# Sensors.net
KiCad netlist of a schematic drawn in Altium Designer
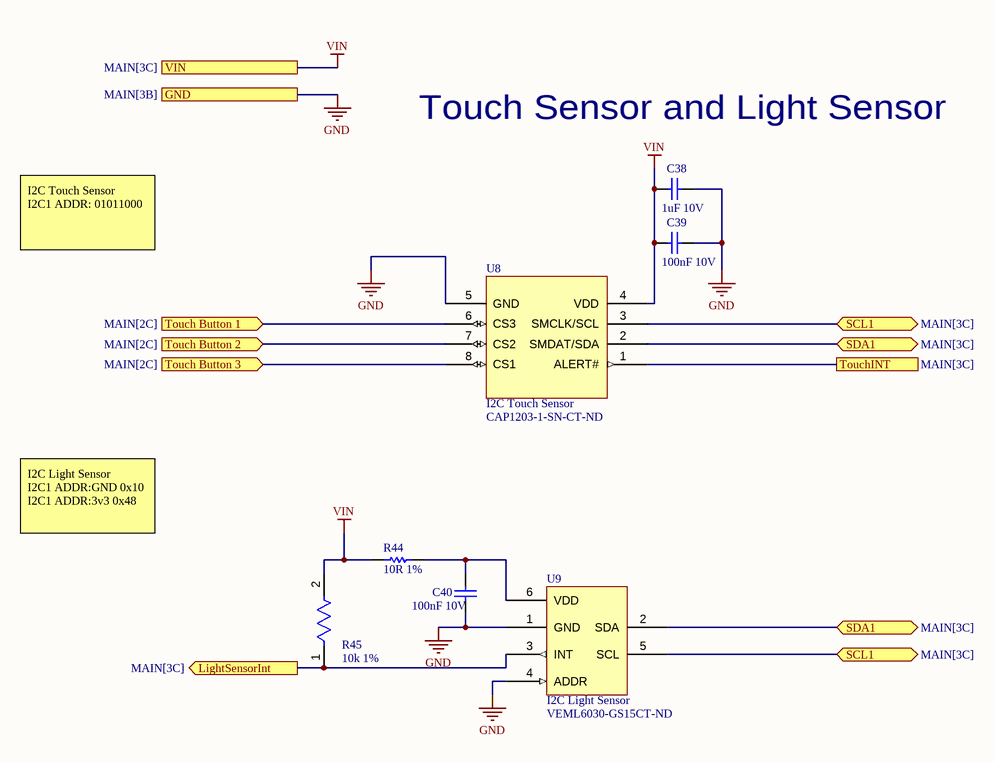
[diagram p0: Sensors.SchDoc]

(export (version "E")
  (design (tool "Eeschema 10.0.6"))
  (components
    (comp (ref "C38")
      (value "1uF 10V")
      (footprint "CAPC0402(1005)60_N")
      (description "CAP 1uF 10V ±10% 0402 (1005 Metric) Thickness 0.6mm SMD")
      (fields (field (name "TOLERANCE") "Â±10%"))
      (libsource (lib "Altium Content Vault") (part "CAP"))
    )
    (comp (ref "C39")
      (value "100nF 10V")
      (footprint "CAPC0402(1005)60_L")
      (description "CAP 100nF 10V ±5% 0402 (1005 Metric) Thickness 0.6mm SMD")
      (fields (field (name "TOLERANCE") "Â±5%"))
      (libsource (lib "Altium Content Vault") (part "CAP"))
    )
    (comp (ref "C40")
      (value "100nF 10V")
      (footprint "CAPC0402(1005)60_L")
      (description "CAP 100nF 10V ±5% 0402 (1005 Metric) Thickness 0.6mm SMD")
      (fields (field (name "TOLERANCE") "Â±5%"))
      (libsource (lib "Altium Content Vault") (part "CAP"))
    )
    (comp (ref "R44")
      (value "10R 1%")
      (footprint "RESC0402(1005)_N")
      (description "10R 0.063W 1% 0402 (1005 Metric)  SMD")
      (fields (field (name "POWER") "0.063 W") (field (name "TOLERANCE") "1 %"))
      (libsource (lib "Altium Content Vault") (part "RES"))
    )
    (comp (ref "R45")
      (value "10k 1%")
      (footprint "FP-CRCW0402-e3-IPC_C")
      (description "RES Thick Film, 10kΩ, 1%, 0.063W, 100ppm/°C, 0402")
      (fields (field (name "TOLERANCE") "1%"))
      (libsource (lib "Altium Content Vault") (part "1029c3af85768c4190bb7ad29bc67b5"))
    )
    (comp (ref "U8")
      (value "I2C Touch Sensor")
      (footprint "CAP1203-1-SN-TR")
      (description "Sensor Controller Capacitive 3-CH I2C 8-Pin SOIC T/R")
      (fields
        (field (name "MANUFACTURER") "Microchip")
        (field (name "MANUFACTURER PART NUMBER") "CAP1203-1-SN-TR")
        (field (name "SUPPLIER PART NUMBER 1") "CAP1203-1-SN-CT-ND")
      )
      (libsource (lib "ESE516A2") (part "CAP1203-1-SN-TR"))
    )
    (comp (ref "U9")
      (value "I2C Light Sensor")
      (footprint "CAC-65P200X200-6N")
      (description "HIGH ACCURACY AMBIENT LIGHT SENS")
      (fields
        (field (name "MANUFACTURER") "Vishay Semiconductors")
        (field (name "MANUFACTURER PART NUMBER") "VEML6030-GS15")
        (field (name "SUPPLIER PART NUMBER 1") "VEML6030-GS15CT-ND")
      )
      (libsource (lib "ESE516A2") (part "VEML6030-GS15"))
    )
  )
  (nets
    (net (code "1") (name "/LightSensorInt") (class "Default")
      (node (ref "R45") (pin "1") (pinfunction "1_1") (pintype "passive"))
      (node (ref "U9") (pin "3") (pinfunction "INT_3") (pintype "output"))
    )
    (net (code "2") (name "/SCL1") (class "Default")
      (node (ref "U8") (pin "3") (pinfunction "SMCLK/SCL_3") (pintype "open_collector"))
      (node (ref "U9") (pin "5") (pinfunction "SCL_5") (pintype "open_collector"))
    )
    (net (code "3") (name "/SDA1") (class "Default")
      (node (ref "U8") (pin "2") (pinfunction "SMDAT/SDA_2") (pintype "open_collector"))
      (node (ref "U9") (pin "2") (pinfunction "SDA_2") (pintype "open_collector"))
    )
    (net (code "4") (name "/Touch Button 1") (class "Default")
      (node (ref "U8") (pin "6") (pinfunction "CS3_6") (pintype "bidirectional"))
    )
    (net (code "5") (name "/Touch Button 2") (class "Default")
      (node (ref "U8") (pin "7") (pinfunction "CS2_7") (pintype "bidirectional"))
    )
    (net (code "6") (name "/Touch Button 3") (class "Default")
      (node (ref "U8") (pin "8") (pinfunction "CS1_8") (pintype "bidirectional"))
    )
    (net (code "7") (name "/TouchINT") (class "Default")
      (node (ref "U8") (pin "1") (pinfunction "ALERT#_1") (pintype "output"))
    )
    (net (code "8") (name "GND") (class "Default")
      (node (ref "C38") (pin "2") (pinfunction "2_2") (pintype "passive"))
      (node (ref "C39") (pin "2") (pinfunction "2_2") (pintype "passive"))
      (node (ref "C40") (pin "1") (pinfunction "1_1") (pintype "passive"))
      (node (ref "U8") (pin "5") (pinfunction "GND_5") (pintype "power_in"))
      (node (ref "U9") (pin "1") (pinfunction "GND_1") (pintype "power_in"))
      (node (ref "U9") (pin "4") (pinfunction "ADDR_4") (pintype "input"))
    )
    (net (code "9") (name "Net-(U9-VDD)") (class "Default")
      (node (ref "C40") (pin "2") (pinfunction "2_2") (pintype "passive"))
      (node (ref "R44") (pin "2") (pinfunction "2_2") (pintype "passive"))
      (node (ref "U9") (pin "6") (pinfunction "VDD_6") (pintype "power_in"))
    )
    (net (code "10") (name "VIN") (class "Default")
      (node (ref "C38") (pin "1") (pinfunction "1_1") (pintype "passive"))
      (node (ref "C39") (pin "1") (pinfunction "1_1") (pintype "passive"))
      (node (ref "R44") (pin "1") (pinfunction "1_1") (pintype "passive"))
      (node (ref "R45") (pin "2") (pinfunction "2_2") (pintype "passive"))
      (node (ref "U8") (pin "4") (pinfunction "VDD_4") (pintype "power_in"))
    )
  )
)
